# 76x40_LED_BOB.net
KiCad netlist of a schematic drawn in EAGLE
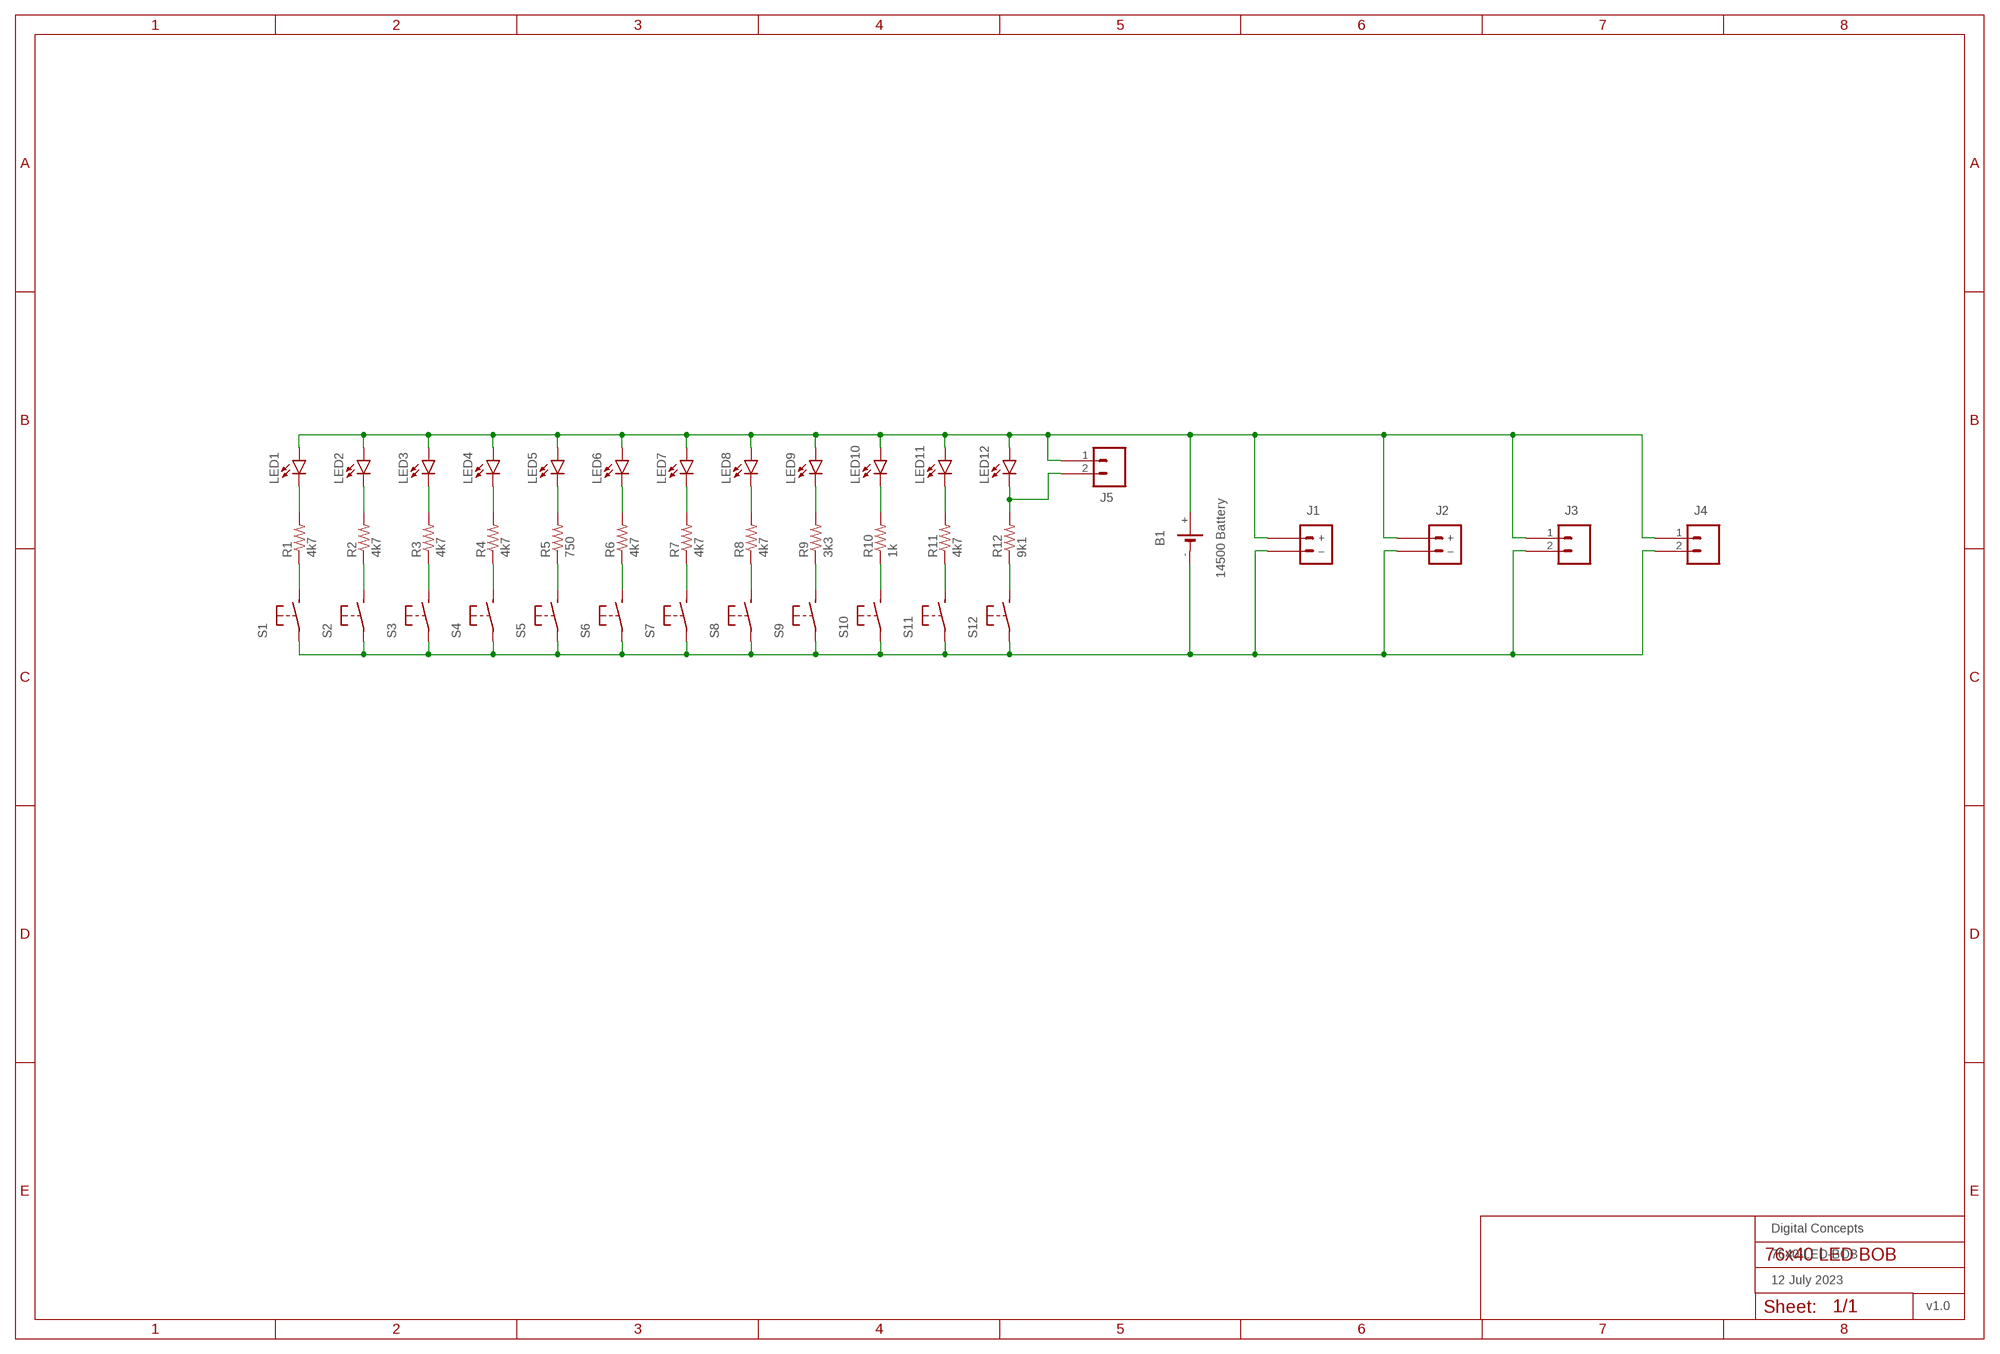
[diagram p0: schematic, sheet 1]

(export (version "E")
  (design (tool "Eeschema 10.0.6"))
  (components
    (comp (ref "B1")
      (value "14500 Battery")
      (footprint "eagle-import:BATTERY-14500")
      (libsource (lib "eagle-import") (part "BATTERY-HOLDER-14500(AA)"))
    )
    (comp (ref "J1")
      (value "JST-PH2.0-2-H-POWER")
      (footprint "eagle-import:JST-PH2.0-2-HORIZONTAL-POWER")
      (libsource (lib "eagle-import") (part "JST-PH2.0-2-H-POWER"))
    )
    (comp (ref "J2")
      (value "JST-GH1.25-2-HORIZONTAL-POWER")
      (footprint "eagle-import:JST-GH1.25-2-HORIZONTAL")
      (libsource (lib "eagle-import") (part "JST-GH1.25-2-HORIZONTAL-POWER"))
    )
    (comp (ref "J3")
      (value "HEADER-1X2-GENERIC")
      (footprint "eagle-import:CONN_02-GENERIC")
      (libsource (lib "eagle-import") (part "HEADER-1X2-GENERIC"))
    )
    (comp (ref "J4")
      (value "HEADER-1X2-GENERIC")
      (footprint "eagle-import:CONN_02-GENERIC")
      (libsource (lib "eagle-import") (part "HEADER-1X2-GENERIC"))
    )
    (comp (ref "J5")
      (value "HEADER-1X2-GENERIC")
      (footprint "eagle-import:CONN_02-GENERIC")
      (libsource (lib "eagle-import") (part "HEADER-1X2-GENERIC"))
    )
    (comp (ref "LED1")
      (value "LEDCHIP-LED0805")
      (footprint "eagle-import:CHIP-LED0805")
      (libsource (lib "eagle-import") (part "LEDCHIP-LED0805"))
    )
    (comp (ref "LED2")
      (value "LEDCHIP-LED0805")
      (footprint "eagle-import:CHIP-LED0805")
      (libsource (lib "eagle-import") (part "LEDCHIP-LED0805"))
    )
    (comp (ref "LED3")
      (value "LEDCHIP-LED0805")
      (footprint "eagle-import:CHIP-LED0805")
      (libsource (lib "eagle-import") (part "LEDCHIP-LED0805"))
    )
    (comp (ref "LED4")
      (value "LEDCHIP-LED0805")
      (footprint "eagle-import:CHIP-LED0805")
      (libsource (lib "eagle-import") (part "LEDCHIP-LED0805"))
    )
    (comp (ref "LED5")
      (value "LEDCHIP-LED0805")
      (footprint "eagle-import:CHIP-LED0805")
      (libsource (lib "eagle-import") (part "LEDCHIP-LED0805"))
    )
    (comp (ref "LED6")
      (value "LEDCHIP-LED0805")
      (footprint "eagle-import:CHIP-LED0805")
      (libsource (lib "eagle-import") (part "LEDCHIP-LED0805"))
    )
    (comp (ref "LED7")
      (value "LEDCHIP-LED0805")
      (footprint "eagle-import:CHIP-LED0805")
      (libsource (lib "eagle-import") (part "LEDCHIP-LED0805"))
    )
    (comp (ref "LED8")
      (value "LEDCHIP-LED0805")
      (footprint "eagle-import:CHIP-LED0805")
      (libsource (lib "eagle-import") (part "LEDCHIP-LED0805"))
    )
    (comp (ref "LED9")
      (value "LEDCHIP-LED0805")
      (footprint "eagle-import:CHIP-LED0805")
      (libsource (lib "eagle-import") (part "LEDCHIP-LED0805"))
    )
    (comp (ref "LED10")
      (value "LEDCHIP-LED0805")
      (footprint "eagle-import:CHIP-LED0805")
      (libsource (lib "eagle-import") (part "LEDCHIP-LED0805"))
    )
    (comp (ref "LED11")
      (value "LEDCHIP-LED0805")
      (footprint "eagle-import:CHIP-LED0805")
      (libsource (lib "eagle-import") (part "LEDCHIP-LED0805"))
    )
    (comp (ref "LED12")
      (value "LEDCHIP-LED0805")
      (footprint "eagle-import:CHIP-LED0805")
      (libsource (lib "eagle-import") (part "LEDCHIP-LED0805"))
    )
    (comp (ref "R1")
      (value "4k7")
      (footprint "eagle-import:R0805")
      (libsource (lib "eagle-import") (part "RESISTORR0805"))
    )
    (comp (ref "R2")
      (value "4k7")
      (footprint "eagle-import:R0805")
      (libsource (lib "eagle-import") (part "RESISTORR0805"))
    )
    (comp (ref "R3")
      (value "4k7")
      (footprint "eagle-import:R0805")
      (libsource (lib "eagle-import") (part "RESISTORR0805"))
    )
    (comp (ref "R4")
      (value "4k7")
      (footprint "eagle-import:R0805")
      (libsource (lib "eagle-import") (part "RESISTORR0805"))
    )
    (comp (ref "R5")
      (value "750")
      (footprint "eagle-import:R0805")
      (libsource (lib "eagle-import") (part "RESISTORR0805"))
    )
    (comp (ref "R6")
      (value "4k7")
      (footprint "eagle-import:R0805")
      (libsource (lib "eagle-import") (part "RESISTORR0805"))
    )
    (comp (ref "R7")
      (value "4k7")
      (footprint "eagle-import:R0805")
      (libsource (lib "eagle-import") (part "RESISTORR0805"))
    )
    (comp (ref "R8")
      (value "4k7")
      (footprint "eagle-import:R0805")
      (libsource (lib "eagle-import") (part "RESISTORR0805"))
    )
    (comp (ref "R9")
      (value "3k3")
      (footprint "eagle-import:R0805")
      (libsource (lib "eagle-import") (part "RESISTORR0805"))
    )
    (comp (ref "R10")
      (value "1k")
      (footprint "eagle-import:R0805")
      (libsource (lib "eagle-import") (part "RESISTORR0805"))
    )
    (comp (ref "R11")
      (value "4k7")
      (footprint "eagle-import:R0805")
      (libsource (lib "eagle-import") (part "RESISTORR0805"))
    )
    (comp (ref "R12")
      (value "9k1")
      (footprint "eagle-import:R0805")
      (libsource (lib "eagle-import") (part "RESISTORR0805"))
    )
    (comp (ref "S1")
      (value "SWITCH-MOMENTARY-2-PIN")
      (footprint "eagle-import:SWITCH-2-PAD")
      (libsource (lib "eagle-import") (part "SWITCH-MOMENTARY-2-PIN"))
    )
    (comp (ref "S2")
      (value "SWITCH-MOMENTARY-2-PIN")
      (footprint "eagle-import:SWITCH-2-PAD")
      (libsource (lib "eagle-import") (part "SWITCH-MOMENTARY-2-PIN"))
    )
    (comp (ref "S3")
      (value "SWITCH-MOMENTARY-2-PIN")
      (footprint "eagle-import:SWITCH-2-PAD")
      (libsource (lib "eagle-import") (part "SWITCH-MOMENTARY-2-PIN"))
    )
    (comp (ref "S4")
      (value "SWITCH-MOMENTARY-2-PIN")
      (footprint "eagle-import:SWITCH-2-PAD")
      (libsource (lib "eagle-import") (part "SWITCH-MOMENTARY-2-PIN"))
    )
    (comp (ref "S5")
      (value "SWITCH-MOMENTARY-2-PIN")
      (footprint "eagle-import:SWITCH-2-PAD")
      (libsource (lib "eagle-import") (part "SWITCH-MOMENTARY-2-PIN"))
    )
    (comp (ref "S6")
      (value "SWITCH-MOMENTARY-2-PIN")
      (footprint "eagle-import:SWITCH-2-PAD")
      (libsource (lib "eagle-import") (part "SWITCH-MOMENTARY-2-PIN"))
    )
    (comp (ref "S7")
      (value "SWITCH-MOMENTARY-2-PIN")
      (footprint "eagle-import:SWITCH-2-PAD")
      (libsource (lib "eagle-import") (part "SWITCH-MOMENTARY-2-PIN"))
    )
    (comp (ref "S8")
      (value "SWITCH-MOMENTARY-2-PIN")
      (footprint "eagle-import:SWITCH-2-PAD")
      (libsource (lib "eagle-import") (part "SWITCH-MOMENTARY-2-PIN"))
    )
    (comp (ref "S9")
      (value "SWITCH-MOMENTARY-2-PIN")
      (footprint "eagle-import:SWITCH-2-PAD")
      (libsource (lib "eagle-import") (part "SWITCH-MOMENTARY-2-PIN"))
    )
    (comp (ref "S10")
      (value "SWITCH-MOMENTARY-2-PIN")
      (footprint "eagle-import:SWITCH-2-PAD")
      (libsource (lib "eagle-import") (part "SWITCH-MOMENTARY-2-PIN"))
    )
    (comp (ref "S11")
      (value "SWITCH-MOMENTARY-2-PIN")
      (footprint "eagle-import:SWITCH-2-PAD")
      (libsource (lib "eagle-import") (part "SWITCH-MOMENTARY-2-PIN"))
    )
    (comp (ref "S12")
      (value "SWITCH-MOMENTARY-2-PIN")
      (footprint "eagle-import:SWITCH-2-PAD")
      (libsource (lib "eagle-import") (part "SWITCH-MOMENTARY-2-PIN"))
    )
  )
  (nets
    (net (code "1") (name "Net-(B1-Pad+)") (class "Default")
      (node (ref "B1") (pin "+") (pinfunction "+_+") (pintype "power_in"))
      (node (ref "J1") (pin "+") (pinfunction "+_+") (pintype "power_in"))
      (node (ref "J2") (pin "+") (pinfunction "+_+") (pintype "power_in"))
      (node (ref "J3") (pin "1") (pinfunction "1_1") (pintype "passive"))
      (node (ref "J4") (pin "1") (pinfunction "1_1") (pintype "passive"))
      (node (ref "J5") (pin "1") (pinfunction "1_1") (pintype "passive"))
      (node (ref "LED1") (pin "A") (pinfunction "A_A") (pintype "passive"))
      (node (ref "LED10") (pin "A") (pinfunction "A_A") (pintype "passive"))
      (node (ref "LED11") (pin "A") (pinfunction "A_A") (pintype "passive"))
      (node (ref "LED12") (pin "A") (pinfunction "A_A") (pintype "passive"))
      (node (ref "LED2") (pin "A") (pinfunction "A_A") (pintype "passive"))
      (node (ref "LED3") (pin "A") (pinfunction "A_A") (pintype "passive"))
      (node (ref "LED4") (pin "A") (pinfunction "A_A") (pintype "passive"))
      (node (ref "LED5") (pin "A") (pinfunction "A_A") (pintype "passive"))
      (node (ref "LED6") (pin "A") (pinfunction "A_A") (pintype "passive"))
      (node (ref "LED7") (pin "A") (pinfunction "A_A") (pintype "passive"))
      (node (ref "LED8") (pin "A") (pinfunction "A_A") (pintype "passive"))
      (node (ref "LED9") (pin "A") (pinfunction "A_A") (pintype "passive"))
    )
    (net (code "2") (name "Net-(J1-–)") (class "Default")
      (node (ref "B1") (pin "-") (pinfunction "-_-") (pintype "power_in"))
      (node (ref "J1") (pin "-") (pinfunction "–_-") (pintype "power_in"))
      (node (ref "J2") (pin "-") (pinfunction "–_-") (pintype "power_in"))
      (node (ref "J3") (pin "2") (pinfunction "2_2") (pintype "passive"))
      (node (ref "J4") (pin "2") (pinfunction "2_2") (pintype "passive"))
      (node (ref "S1") (pin "P$1") (pinfunction "P_P$1") (pintype "passive"))
      (node (ref "S10") (pin "P$1") (pinfunction "P_P$1") (pintype "passive"))
      (node (ref "S11") (pin "P$1") (pinfunction "P_P$1") (pintype "passive"))
      (node (ref "S12") (pin "P$1") (pinfunction "P_P$1") (pintype "passive"))
      (node (ref "S2") (pin "P$1") (pinfunction "P_P$1") (pintype "passive"))
      (node (ref "S3") (pin "P$1") (pinfunction "P_P$1") (pintype "passive"))
      (node (ref "S4") (pin "P$1") (pinfunction "P_P$1") (pintype "passive"))
      (node (ref "S5") (pin "P$1") (pinfunction "P_P$1") (pintype "passive"))
      (node (ref "S6") (pin "P$1") (pinfunction "P_P$1") (pintype "passive"))
      (node (ref "S7") (pin "P$1") (pinfunction "P_P$1") (pintype "passive"))
      (node (ref "S8") (pin "P$1") (pinfunction "P_P$1") (pintype "passive"))
      (node (ref "S9") (pin "P$1") (pinfunction "P_P$1") (pintype "passive"))
    )
    (net (code "3") (name "Net-(J5-Pad2)") (class "Default")
      (node (ref "J5") (pin "2") (pinfunction "2_2") (pintype "passive"))
      (node (ref "LED12") (pin "C") (pinfunction "C_C") (pintype "passive"))
      (node (ref "R12") (pin "2") (pinfunction "2_2") (pintype "passive"))
    )
    (net (code "4") (name "Net-(LED1-PadC)") (class "Default")
      (node (ref "LED1") (pin "C") (pinfunction "C_C") (pintype "passive"))
      (node (ref "R1") (pin "2") (pinfunction "2_2") (pintype "passive"))
    )
    (net (code "5") (name "Net-(LED2-PadC)") (class "Default")
      (node (ref "LED2") (pin "C") (pinfunction "C_C") (pintype "passive"))
      (node (ref "R2") (pin "2") (pinfunction "2_2") (pintype "passive"))
    )
    (net (code "6") (name "Net-(LED3-PadC)") (class "Default")
      (node (ref "LED3") (pin "C") (pinfunction "C_C") (pintype "passive"))
      (node (ref "R3") (pin "2") (pinfunction "2_2") (pintype "passive"))
    )
    (net (code "7") (name "Net-(LED4-PadC)") (class "Default")
      (node (ref "LED4") (pin "C") (pinfunction "C_C") (pintype "passive"))
      (node (ref "R4") (pin "2") (pinfunction "2_2") (pintype "passive"))
    )
    (net (code "8") (name "Net-(LED5-PadC)") (class "Default")
      (node (ref "LED5") (pin "C") (pinfunction "C_C") (pintype "passive"))
      (node (ref "R5") (pin "2") (pinfunction "2_2") (pintype "passive"))
    )
    (net (code "9") (name "Net-(LED6-PadC)") (class "Default")
      (node (ref "LED6") (pin "C") (pinfunction "C_C") (pintype "passive"))
      (node (ref "R6") (pin "2") (pinfunction "2_2") (pintype "passive"))
    )
    (net (code "10") (name "Net-(LED7-PadC)") (class "Default")
      (node (ref "LED7") (pin "C") (pinfunction "C_C") (pintype "passive"))
      (node (ref "R7") (pin "2") (pinfunction "2_2") (pintype "passive"))
    )
    (net (code "11") (name "Net-(LED8-PadC)") (class "Default")
      (node (ref "LED8") (pin "C") (pinfunction "C_C") (pintype "passive"))
      (node (ref "R8") (pin "2") (pinfunction "2_2") (pintype "passive"))
    )
    (net (code "12") (name "Net-(LED9-PadC)") (class "Default")
      (node (ref "LED9") (pin "C") (pinfunction "C_C") (pintype "passive"))
      (node (ref "R9") (pin "2") (pinfunction "2_2") (pintype "passive"))
    )
    (net (code "13") (name "Net-(LED10-PadC)") (class "Default")
      (node (ref "LED10") (pin "C") (pinfunction "C_C") (pintype "passive"))
      (node (ref "R10") (pin "2") (pinfunction "2_2") (pintype "passive"))
    )
    (net (code "14") (name "Net-(LED11-PadC)") (class "Default")
      (node (ref "LED11") (pin "C") (pinfunction "C_C") (pintype "passive"))
      (node (ref "R11") (pin "2") (pinfunction "2_2") (pintype "passive"))
    )
    (net (code "15") (name "Net-(S1-S)") (class "Default")
      (node (ref "R1") (pin "1") (pinfunction "1_1") (pintype "passive"))
      (node (ref "S1") (pin "P$2") (pinfunction "S_P$2") (pintype "passive"))
    )
    (net (code "16") (name "Net-(S2-S)") (class "Default")
      (node (ref "R2") (pin "1") (pinfunction "1_1") (pintype "passive"))
      (node (ref "S2") (pin "P$2") (pinfunction "S_P$2") (pintype "passive"))
    )
    (net (code "17") (name "Net-(S3-S)") (class "Default")
      (node (ref "R3") (pin "1") (pinfunction "1_1") (pintype "passive"))
      (node (ref "S3") (pin "P$2") (pinfunction "S_P$2") (pintype "passive"))
    )
    (net (code "18") (name "Net-(S4-S)") (class "Default")
      (node (ref "R4") (pin "1") (pinfunction "1_1") (pintype "passive"))
      (node (ref "S4") (pin "P$2") (pinfunction "S_P$2") (pintype "passive"))
    )
    (net (code "19") (name "Net-(S5-S)") (class "Default")
      (node (ref "R5") (pin "1") (pinfunction "1_1") (pintype "passive"))
      (node (ref "S5") (pin "P$2") (pinfunction "S_P$2") (pintype "passive"))
    )
    (net (code "20") (name "Net-(S6-S)") (class "Default")
      (node (ref "R6") (pin "1") (pinfunction "1_1") (pintype "passive"))
      (node (ref "S6") (pin "P$2") (pinfunction "S_P$2") (pintype "passive"))
    )
    (net (code "21") (name "Net-(S7-S)") (class "Default")
      (node (ref "R7") (pin "1") (pinfunction "1_1") (pintype "passive"))
      (node (ref "S7") (pin "P$2") (pinfunction "S_P$2") (pintype "passive"))
    )
    (net (code "22") (name "Net-(S8-S)") (class "Default")
      (node (ref "R8") (pin "1") (pinfunction "1_1") (pintype "passive"))
      (node (ref "S8") (pin "P$2") (pinfunction "S_P$2") (pintype "passive"))
    )
    (net (code "23") (name "Net-(S9-S)") (class "Default")
      (node (ref "R9") (pin "1") (pinfunction "1_1") (pintype "passive"))
      (node (ref "S9") (pin "P$2") (pinfunction "S_P$2") (pintype "passive"))
    )
    (net (code "24") (name "Net-(S10-S)") (class "Default")
      (node (ref "R10") (pin "1") (pinfunction "1_1") (pintype "passive"))
      (node (ref "S10") (pin "P$2") (pinfunction "S_P$2") (pintype "passive"))
    )
    (net (code "25") (name "Net-(S11-S)") (class "Default")
      (node (ref "R11") (pin "1") (pinfunction "1_1") (pintype "passive"))
      (node (ref "S11") (pin "P$2") (pinfunction "S_P$2") (pintype "passive"))
    )
    (net (code "26") (name "Net-(S12-S)") (class "Default")
      (node (ref "R12") (pin "1") (pinfunction "1_1") (pintype "passive"))
      (node (ref "S12") (pin "P$2") (pinfunction "S_P$2") (pintype "passive"))
    )
  )
)
